# ROV_HAT_sceem.net
KiCad netlist of a schematic drawn in EAGLE
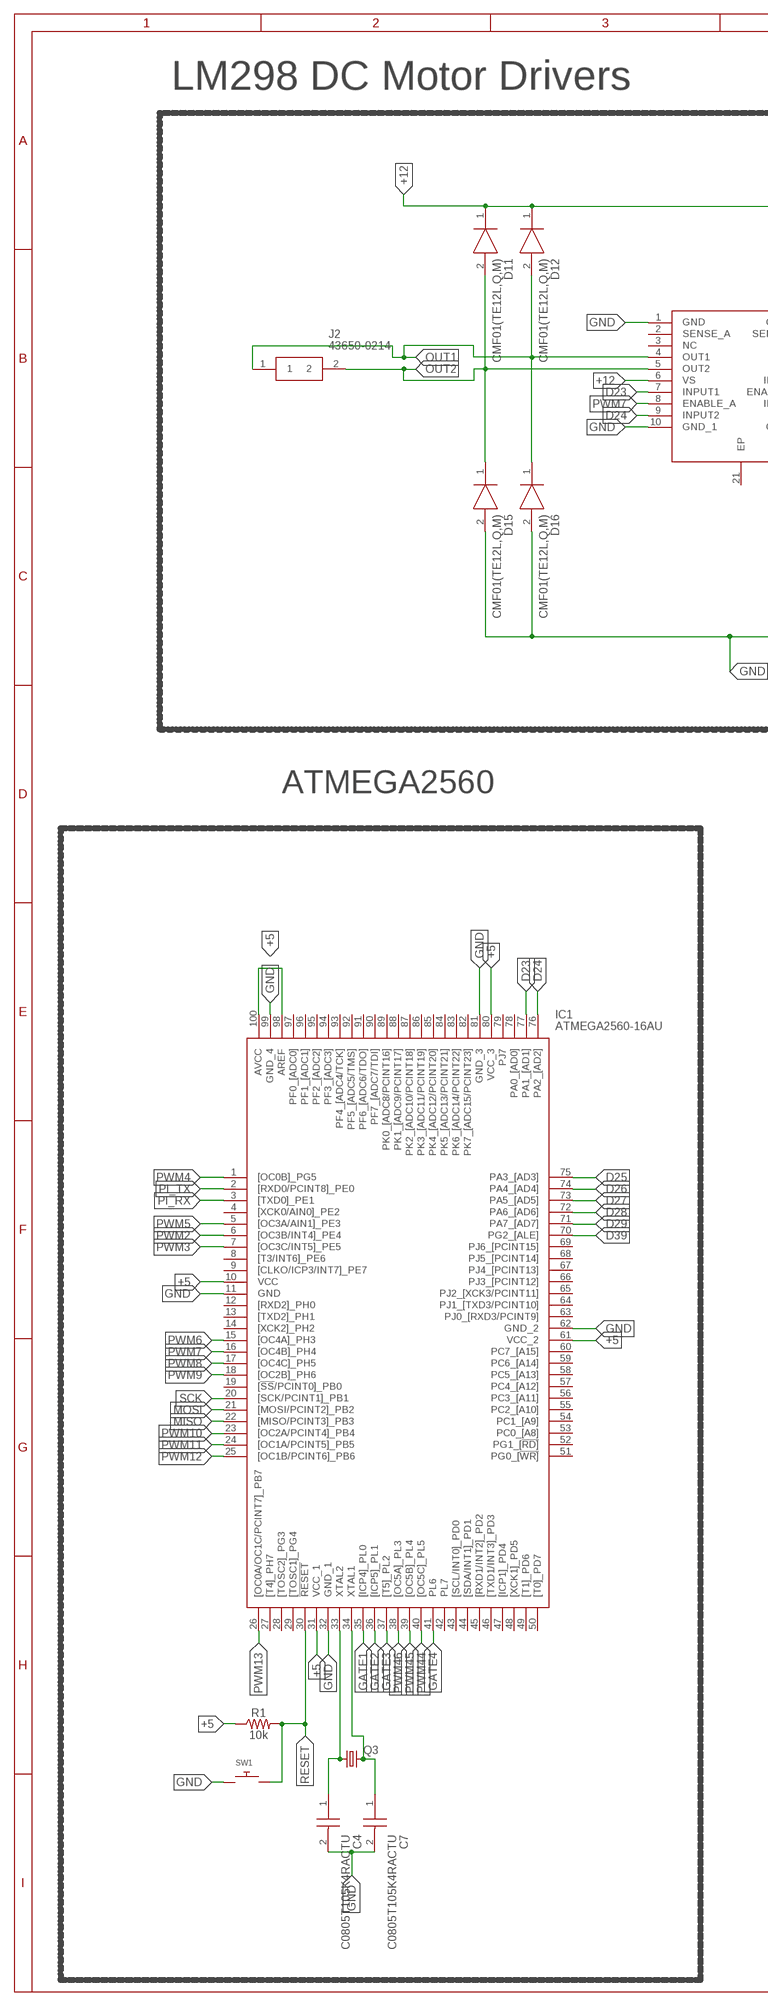
[diagram p0: schematic, sheet 1, part 1 of 2]
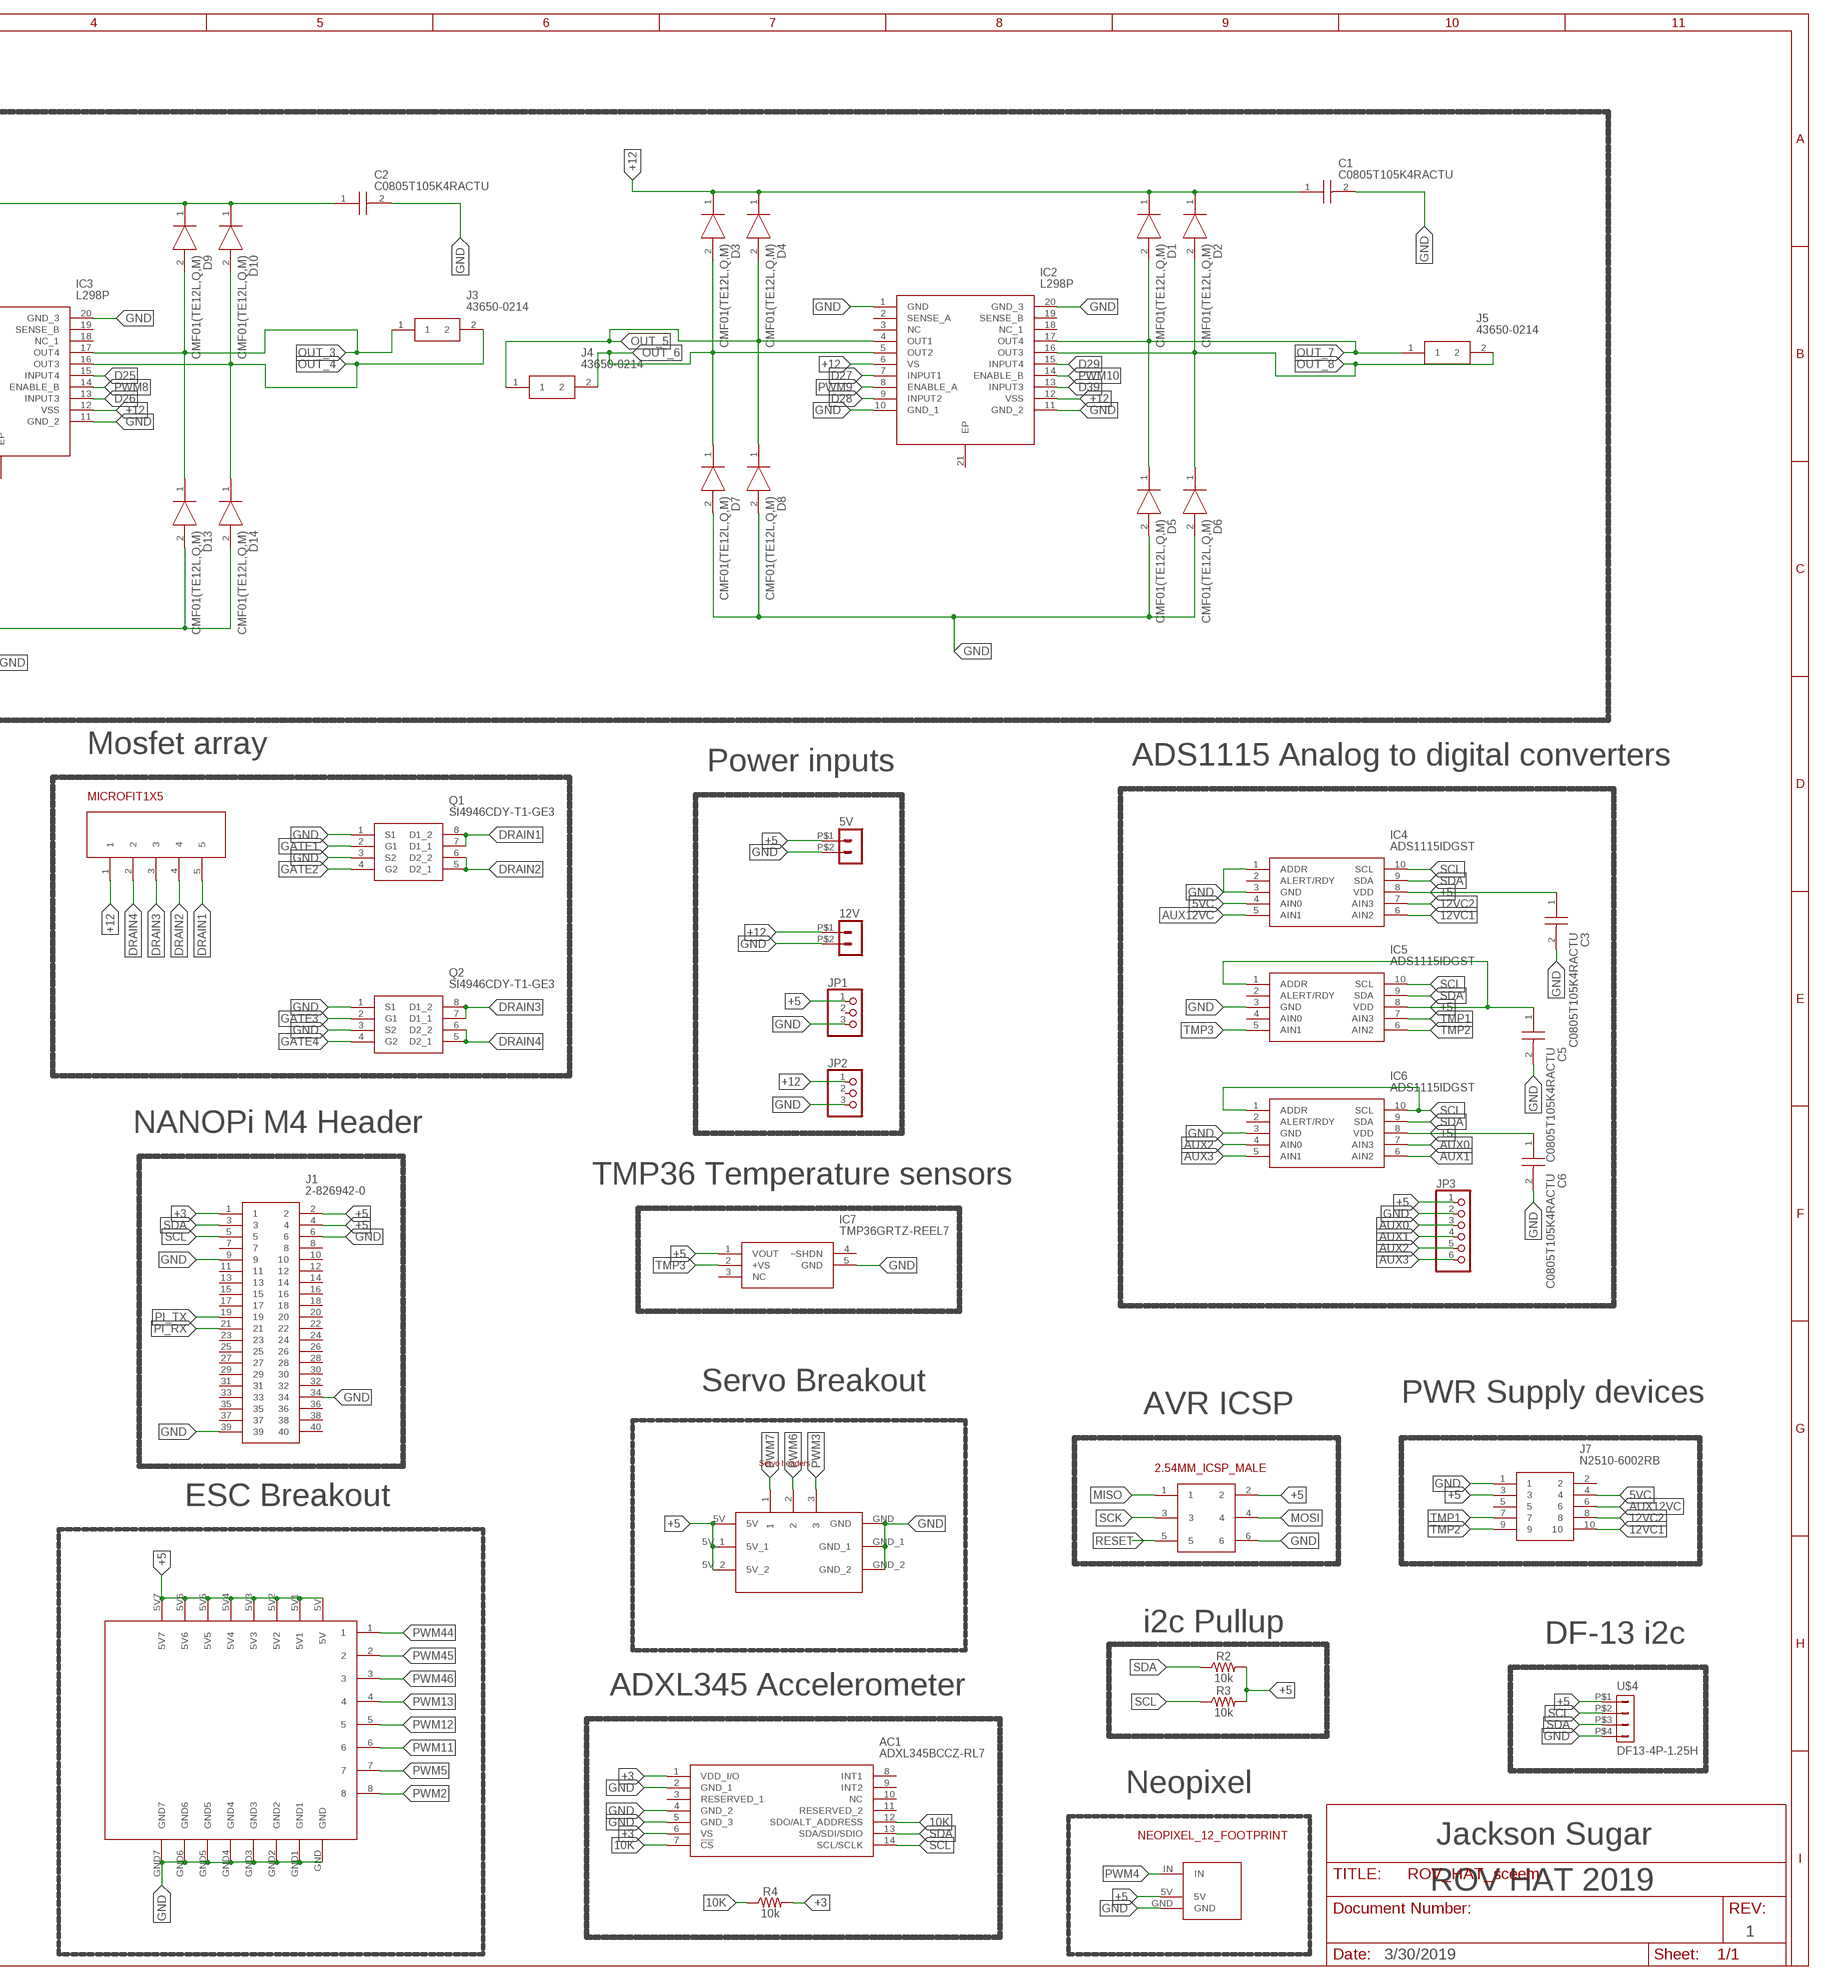
[diagram p1: schematic, sheet 1, part 2 of 2]

(export (version "E")
  (design (tool "Eeschema 10.0.6"))
  (components
    (comp (ref "5V")
      (value "HEADER_POS2_43045-0200")
      (footprint "eagle-import:43045-0200")
      (libsource (lib "eagle-import") (part "HEADER_POS2_?43045-0200"))
    )
    (comp (ref "12V")
      (value "HEADER_POS2_43650-0200")
      (footprint "eagle-import:43650-0200")
      (libsource (lib "eagle-import") (part "HEADER_POS2_?43650-0200"))
    )
    (comp (ref "AC1")
      (value "ADXL345BCCZ-RL7")
      (footprint "eagle-import:CC-14-1")
      (fields (field (name "MOUSER_PART_NUMBER") "584-ADXL345BCCZ-R7"))
      (libsource (lib "eagle-import") (part "ADXL345BCCZ-RL7"))
    )
    (comp (ref "C1")
      (value "C0805T105K4RACTU")
      (footprint "eagle-import:CAPC2012X100N")
      (fields (field (name "MOUSER_PART_NUMBER") "80-C0805T105K4RACTU"))
      (libsource (lib "eagle-import") (part "C0805T105K4RACTU"))
    )
    (comp (ref "C2")
      (value "C0805T105K4RACTU")
      (footprint "eagle-import:CAPC2012X100N")
      (fields (field (name "MOUSER_PART_NUMBER") "80-C0805T105K4RACTU"))
      (libsource (lib "eagle-import") (part "C0805T105K4RACTU"))
    )
    (comp (ref "C3")
      (value "C0805T105K4RACTU")
      (footprint "eagle-import:CAPC2012X100N")
      (fields (field (name "MOUSER_PART_NUMBER") "80-C0805T105K4RACTU"))
      (libsource (lib "eagle-import") (part "C0805T105K4RACTU"))
    )
    (comp (ref "C4")
      (value "C0805T105K4RACTU")
      (footprint "eagle-import:CAPC2012X100N")
      (fields (field (name "MOUSER_PART_NUMBER") "80-C0805T105K4RACTU"))
      (libsource (lib "eagle-import") (part "C0805T105K4RACTU"))
    )
    (comp (ref "C5")
      (value "C0805T105K4RACTU")
      (footprint "eagle-import:CAPC2012X100N")
      (fields (field (name "MOUSER_PART_NUMBER") "80-C0805T105K4RACTU"))
      (libsource (lib "eagle-import") (part "C0805T105K4RACTU"))
    )
    (comp (ref "C6")
      (value "C0805T105K4RACTU")
      (footprint "eagle-import:CAPC2012X100N")
      (fields (field (name "MOUSER_PART_NUMBER") "80-C0805T105K4RACTU"))
      (libsource (lib "eagle-import") (part "C0805T105K4RACTU"))
    )
    (comp (ref "C7")
      (value "C0805T105K4RACTU")
      (footprint "eagle-import:CAPC2012X100N")
      (fields (field (name "MOUSER_PART_NUMBER") "80-C0805T105K4RACTU"))
      (libsource (lib "eagle-import") (part "C0805T105K4RACTU"))
    )
    (comp (ref "D1")
      (value "CMF01(TE12L,Q,M)")
      (footprint "eagle-import:SODFL4724X108N")
      (fields (field (name "MOUSER_PART_NUMBER") "757-CMF01TE12LQM"))
      (libsource (lib "eagle-import") (part "CMF01(TE12L,Q,M)"))
    )
    (comp (ref "D2")
      (value "CMF01(TE12L,Q,M)")
      (footprint "eagle-import:SODFL4724X108N")
      (fields (field (name "MOUSER_PART_NUMBER") "757-CMF01TE12LQM"))
      (libsource (lib "eagle-import") (part "CMF01(TE12L,Q,M)"))
    )
    (comp (ref "D3")
      (value "CMF01(TE12L,Q,M)")
      (footprint "eagle-import:SODFL4724X108N")
      (fields (field (name "MOUSER_PART_NUMBER") "757-CMF01TE12LQM"))
      (libsource (lib "eagle-import") (part "CMF01(TE12L,Q,M)"))
    )
    (comp (ref "D4")
      (value "CMF01(TE12L,Q,M)")
      (footprint "eagle-import:SODFL4724X108N")
      (fields (field (name "MOUSER_PART_NUMBER") "757-CMF01TE12LQM"))
      (libsource (lib "eagle-import") (part "CMF01(TE12L,Q,M)"))
    )
    (comp (ref "D5")
      (value "CMF01(TE12L,Q,M)")
      (footprint "eagle-import:SODFL4724X108N")
      (fields (field (name "MOUSER_PART_NUMBER") "757-CMF01TE12LQM"))
      (libsource (lib "eagle-import") (part "CMF01(TE12L,Q,M)"))
    )
    (comp (ref "D6")
      (value "CMF01(TE12L,Q,M)")
      (footprint "eagle-import:SODFL4724X108N")
      (fields (field (name "MOUSER_PART_NUMBER") "757-CMF01TE12LQM"))
      (libsource (lib "eagle-import") (part "CMF01(TE12L,Q,M)"))
    )
    (comp (ref "D7")
      (value "CMF01(TE12L,Q,M)")
      (footprint "eagle-import:SODFL4724X108N")
      (fields (field (name "MOUSER_PART_NUMBER") "757-CMF01TE12LQM"))
      (libsource (lib "eagle-import") (part "CMF01(TE12L,Q,M)"))
    )
    (comp (ref "D8")
      (value "CMF01(TE12L,Q,M)")
      (footprint "eagle-import:SODFL4724X108N")
      (fields (field (name "MOUSER_PART_NUMBER") "757-CMF01TE12LQM"))
      (libsource (lib "eagle-import") (part "CMF01(TE12L,Q,M)"))
    )
    (comp (ref "D9")
      (value "CMF01(TE12L,Q,M)")
      (footprint "eagle-import:SODFL4724X108N")
      (fields (field (name "MOUSER_PART_NUMBER") "757-CMF01TE12LQM"))
      (libsource (lib "eagle-import") (part "CMF01(TE12L,Q,M)"))
    )
    (comp (ref "D10")
      (value "CMF01(TE12L,Q,M)")
      (footprint "eagle-import:SODFL4724X108N")
      (fields (field (name "MOUSER_PART_NUMBER") "757-CMF01TE12LQM"))
      (libsource (lib "eagle-import") (part "CMF01(TE12L,Q,M)"))
    )
    (comp (ref "D11")
      (value "CMF01(TE12L,Q,M)")
      (footprint "eagle-import:SODFL4724X108N")
      (fields (field (name "MOUSER_PART_NUMBER") "757-CMF01TE12LQM"))
      (libsource (lib "eagle-import") (part "CMF01(TE12L,Q,M)"))
    )
    (comp (ref "D12")
      (value "CMF01(TE12L,Q,M)")
      (footprint "eagle-import:SODFL4724X108N")
      (fields (field (name "MOUSER_PART_NUMBER") "757-CMF01TE12LQM"))
      (libsource (lib "eagle-import") (part "CMF01(TE12L,Q,M)"))
    )
    (comp (ref "D13")
      (value "CMF01(TE12L,Q,M)")
      (footprint "eagle-import:SODFL4724X108N")
      (fields (field (name "MOUSER_PART_NUMBER") "757-CMF01TE12LQM"))
      (libsource (lib "eagle-import") (part "CMF01(TE12L,Q,M)"))
    )
    (comp (ref "D14")
      (value "CMF01(TE12L,Q,M)")
      (footprint "eagle-import:SODFL4724X108N")
      (fields (field (name "MOUSER_PART_NUMBER") "757-CMF01TE12LQM"))
      (libsource (lib "eagle-import") (part "CMF01(TE12L,Q,M)"))
    )
    (comp (ref "D15")
      (value "CMF01(TE12L,Q,M)")
      (footprint "eagle-import:SODFL4724X108N")
      (fields (field (name "MOUSER_PART_NUMBER") "757-CMF01TE12LQM"))
      (libsource (lib "eagle-import") (part "CMF01(TE12L,Q,M)"))
    )
    (comp (ref "D16")
      (value "CMF01(TE12L,Q,M)")
      (footprint "eagle-import:SODFL4724X108N")
      (fields (field (name "MOUSER_PART_NUMBER") "757-CMF01TE12LQM"))
      (libsource (lib "eagle-import") (part "CMF01(TE12L,Q,M)"))
    )
    (comp (ref "IC1")
      (value "ATMEGA2560-16AU")
      (footprint "eagle-import:QFP50P1600X1600X120-100N")
      (fields (field (name "MOUSER_PART_NUMBER") "556-ATMEGA2560-16AU"))
      (libsource (lib "eagle-import") (part "ATMEGA2560-16AU"))
    )
    (comp (ref "IC2")
      (value "L298P")
      (footprint "eagle-import:SOIC127P1420X360-21N")
      (fields (field (name "MOUSER_PART_NUMBER") "511-L298P"))
      (libsource (lib "eagle-import") (part "L298P"))
    )
    (comp (ref "IC3")
      (value "L298P")
      (footprint "eagle-import:SOIC127P1420X360-21N")
      (fields (field (name "MOUSER_PART_NUMBER") "511-L298P"))
      (libsource (lib "eagle-import") (part "L298P"))
    )
    (comp (ref "IC4")
      (value "ADS1115IDGST")
      (footprint "eagle-import:SOP50P490X110-10N")
      (fields (field (name "MOUSER_PART_NUMBER") "595-ADS1115IDGST"))
      (libsource (lib "eagle-import") (part "ADS1115IDGST"))
    )
    (comp (ref "IC5")
      (value "ADS1115IDGST")
      (footprint "eagle-import:SOP50P490X110-10N")
      (fields (field (name "MOUSER_PART_NUMBER") "595-ADS1115IDGST"))
      (libsource (lib "eagle-import") (part "ADS1115IDGST"))
    )
    (comp (ref "IC6")
      (value "ADS1115IDGST")
      (footprint "eagle-import:SOP50P490X110-10N")
      (fields (field (name "MOUSER_PART_NUMBER") "595-ADS1115IDGST"))
      (libsource (lib "eagle-import") (part "ADS1115IDGST"))
    )
    (comp (ref "IC7")
      (value "TMP36GRTZ-REEL7")
      (footprint "eagle-import:SOT95P280X145-5N")
      (fields (field (name "MOUSER_PART_NUMBER") "584-TMP36GRTZ-R7"))
      (libsource (lib "eagle-import") (part "TMP36GRTZ-REEL7"))
    )
    (comp (ref "J1")
      (value "2-826942-0")
      (footprint "eagle-import:HDRV40W63P254_2X20_5080X500X88")
      (fields (field (name "MOUSER_PART_NUMBER") "571-2-826942-0"))
      (libsource (lib "eagle-import") (part "2-826942-0"))
    )
    (comp (ref "J2")
      (value "43650-0214")
      (footprint "eagle-import:43650-0214")
      (fields (field (name "MOUSER_PART_NUMBER") "538-43650-0214"))
      (libsource (lib "eagle-import") (part "43650-0214"))
    )
    (comp (ref "J3")
      (value "43650-0214")
      (footprint "eagle-import:43650-0214")
      (fields (field (name "MOUSER_PART_NUMBER") "538-43650-0214"))
      (libsource (lib "eagle-import") (part "43650-0214"))
    )
    (comp (ref "J4")
      (value "43650-0214")
      (footprint "eagle-import:43650-0214")
      (fields (field (name "MOUSER_PART_NUMBER") "538-43650-0214"))
      (libsource (lib "eagle-import") (part "43650-0214"))
    )
    (comp (ref "J5")
      (value "43650-0214")
      (footprint "eagle-import:43650-0214")
      (fields (field (name "MOUSER_PART_NUMBER") "538-43650-0214"))
      (libsource (lib "eagle-import") (part "43650-0214"))
    )
    (comp (ref "J7")
      (value "N2510-6002RB")
      (footprint "eagle-import:SHDR10W64P254_2X5_2002X859X100")
      (fields (field (name "MOUSER_PART_NUMBER") "517-N2510-6002RB"))
      (libsource (lib "eagle-import") (part "N2510-6002RB"))
    )
    (comp (ref "JP1")
      (value "PINHD-1X3")
      (footprint "eagle-import:1X03")
      (libsource (lib "eagle-import") (part "PINHD-1X3"))
    )
    (comp (ref "JP2")
      (value "PINHD-1X3")
      (footprint "eagle-import:1X03")
      (libsource (lib "eagle-import") (part "PINHD-1X3"))
    )
    (comp (ref "JP3")
      (value "PINHD-1X6")
      (footprint "eagle-import:1X06")
      (libsource (lib "eagle-import") (part "PINHD-1X6"))
    )
    (comp (ref "Q1")
      (value "SI4946CDY-T1-GE3")
      (footprint "eagle-import:SOIC127P600X175-8N")
      (fields (field (name "MOUSER_PART_NUMBER") "78-SI4946CDY-T1-GE3"))
      (libsource (lib "eagle-import") (part "SI4946CDY-T1-GE3"))
    )
    (comp (ref "Q2")
      (value "SI4946CDY-T1-GE3")
      (footprint "eagle-import:SOIC127P600X175-8N")
      (fields (field (name "MOUSER_PART_NUMBER") "78-SI4946CDY-T1-GE3"))
      (libsource (lib "eagle-import") (part "SI4946CDY-T1-GE3"))
    )
    (comp (ref "Q3")
      (value "CRYSTALHC49S")
      (footprint "eagle-import:HC49_S")
      (libsource (lib "eagle-import") (part "CRYSTALHC49S"))
    )
    (comp (ref "R1")
      (value "10k")
      (footprint "eagle-import:0603")
      (libsource (lib "eagle-import") (part "10KOHM-0603-1/10W-1%"))
    )
    (comp (ref "R2")
      (value "10k")
      (footprint "eagle-import:0603")
      (libsource (lib "eagle-import") (part "10KOHM-0603-1/10W-1%"))
    )
    (comp (ref "R3")
      (value "10k")
      (footprint "eagle-import:0603")
      (libsource (lib "eagle-import") (part "10KOHM-0603-1/10W-1%"))
    )
    (comp (ref "R4")
      (value "10k")
      (footprint "eagle-import:0603")
      (libsource (lib "eagle-import") (part "10KOHM-0603-1/10W-1%"))
    )
    (comp (ref "SW1")
      (value "SWITCH_PUSHBUTTONC&K_KSS")
      (footprint "eagle-import:BTN_CK_KSS")
      (libsource (lib "eagle-import") (part "SWITCH_PUSHBUTTONC&K_KSS"))
    )
    (comp (ref "U$1")
      (value "3X8_RIGHT_HEADER")
      (footprint "eagle-import:3X8_RIGHT_HEADER")
      (libsource (lib "eagle-import") (part "3X8_RIGHT_HEADER"))
    )
    (comp (ref "U$2")
      (value "2.54MM_ICSP_MALE")
      (footprint "eagle-import:2.54MM_ICSP_MALE")
      (libsource (lib "eagle-import") (part "2.54MM_ICSP_MALE"))
    )
    (comp (ref "U$3")
      (value "NEOPIXEL_12_FOOTPRINT")
      (footprint "eagle-import:NEOPIXEL_12_FOOTPRINT")
      (libsource (lib "eagle-import") (part "NEOPIXEL_12_FOOTPRINT"))
    )
    (comp (ref "U$4")
      (value "DF13-4P-1.25H")
      (footprint "eagle-import:DF13A-4P-1.25H")
      (libsource (lib "eagle-import") (part "DF13-4P-1.25H"))
    )
    (comp (ref "U$5")
      (value "SERVO_PWM_HEADER")
      (footprint "eagle-import:SERVO_PWM_HEADER")
      (libsource (lib "eagle-import") (part "SERVO_PWM_HEADER"))
    )
    (comp (ref "U$6")
      (value "MICROFIT1X5")
      (footprint "eagle-import:MICROFIT1X5")
      (libsource (lib "eagle-import") (part "MICROFIT1X5"))
    )
  )
  (nets
    (net (code "1") (name "+3") (class "Default")
      (node (ref "AC1") (pin "1") (pinfunction "VDD_I/O_1") (pintype "bidirectional"))
      (node (ref "AC1") (pin "6") (pinfunction "VS_6") (pintype "bidirectional"))
      (node (ref "J1") (pin "1") (pinfunction "1_1") (pintype "bidirectional"))
      (node (ref "R4") (pin "2") (pinfunction "2_2") (pintype "passive"))
    )
    (net (code "2") (name "+5") (class "Default")
      (node (ref "5V") (pin "P$1") (pinfunction "1_P$1") (pintype "passive"))
      (node (ref "C3") (pin "1") (pinfunction "1_1") (pintype "bidirectional"))
      (node (ref "C5") (pin "1") (pinfunction "1_1") (pintype "bidirectional"))
      (node (ref "C6") (pin "1") (pinfunction "1_1") (pintype "bidirectional"))
      (node (ref "IC1") (pin "10") (pinfunction "VCC_10") (pintype "power_in"))
      (node (ref "IC1") (pin "100") (pinfunction "AVCC_100") (pintype "power_in"))
      (node (ref "IC1") (pin "31") (pinfunction "VCC_1_31") (pintype "power_in"))
      (node (ref "IC1") (pin "61") (pinfunction "VCC_2_61") (pintype "power_in"))
      (node (ref "IC1") (pin "80") (pinfunction "VCC_3_80") (pintype "power_in"))
      (node (ref "IC1") (pin "98") (pinfunction "AREF_98") (pintype "input"))
      (node (ref "IC4") (pin "8") (pinfunction "VDD_8") (pintype "power_in"))
      (node (ref "IC5") (pin "1") (pinfunction "ADDR_1") (pintype "bidirectional"))
      (node (ref "IC5") (pin "8") (pinfunction "VDD_8") (pintype "power_in"))
      (node (ref "IC6") (pin "8") (pinfunction "VDD_8") (pintype "power_in"))
      (node (ref "IC7") (pin "1") (pinfunction "VOUT_1") (pintype "bidirectional"))
      (node (ref "J1") (pin "2") (pinfunction "2_2") (pintype "bidirectional"))
      (node (ref "J1") (pin "4") (pinfunction "4_4") (pintype "bidirectional"))
      (node (ref "J7") (pin "3") (pinfunction "3_3") (pintype "bidirectional"))
      (node (ref "JP1") (pin "1") (pinfunction "1_1") (pintype "passive"))
      (node (ref "JP3") (pin "1") (pinfunction "1_1") (pintype "passive"))
      (node (ref "R1") (pin "1") (pinfunction "1_1") (pintype "passive"))
      (node (ref "R2") (pin "2") (pinfunction "2_2") (pintype "passive"))
      (node (ref "R3") (pin "2") (pinfunction "2_2") (pintype "passive"))
      (node (ref "U$1") (pin "5V") (pinfunction "5V_5V") (pintype "bidirectional"))
      (node (ref "U$1") (pin "5V1") (pinfunction "5V1_5V1") (pintype "bidirectional"))
      (node (ref "U$1") (pin "5V2") (pinfunction "5V2_5V2") (pintype "bidirectional"))
      (node (ref "U$1") (pin "5V3") (pinfunction "5V3_5V3") (pintype "bidirectional"))
      (node (ref "U$1") (pin "5V4") (pinfunction "5V4_5V4") (pintype "bidirectional"))
      (node (ref "U$1") (pin "5V5") (pinfunction "5V5_5V5") (pintype "bidirectional"))
      (node (ref "U$1") (pin "5V6") (pinfunction "5V6_5V6") (pintype "bidirectional"))
      (node (ref "U$1") (pin "5V7") (pinfunction "5V7_5V7") (pintype "bidirectional"))
      (node (ref "U$2") (pin "2") (pinfunction "2_2") (pintype "bidirectional"))
      (node (ref "U$3") (pin "5V") (pinfunction "5V_5V") (pintype "bidirectional"))
      (node (ref "U$4") (pin "P$1") (pinfunction "1_P$1") (pintype "passive"))
      (node (ref "U$5") (pin "5V") (pinfunction "5V_5V") (pintype "bidirectional"))
      (node (ref "U$5") (pin "5V_1") (pinfunction "5V_1_5V_1") (pintype "bidirectional"))
      (node (ref "U$5") (pin "5V_2") (pinfunction "5V_2_5V_2") (pintype "bidirectional"))
    )
    (net (code "3") (name "+12") (class "Default")
      (node (ref "12V") (pin "P$1") (pinfunction "1_P$1") (pintype "passive"))
      (node (ref "C1") (pin "1") (pinfunction "1_1") (pintype "bidirectional"))
      (node (ref "C2") (pin "1") (pinfunction "1_1") (pintype "bidirectional"))
      (node (ref "D1") (pin "1") (pinfunction "K_1") (pintype "bidirectional"))
      (node (ref "D10") (pin "1") (pinfunction "K_1") (pintype "bidirectional"))
      (node (ref "D11") (pin "1") (pinfunction "K_1") (pintype "bidirectional"))
      (node (ref "D12") (pin "1") (pinfunction "K_1") (pintype "bidirectional"))
      (node (ref "D2") (pin "1") (pinfunction "K_1") (pintype "bidirectional"))
      (node (ref "D3") (pin "1") (pinfunction "K_1") (pintype "bidirectional"))
      (node (ref "D4") (pin "1") (pinfunction "K_1") (pintype "bidirectional"))
      (node (ref "D9") (pin "1") (pinfunction "K_1") (pintype "bidirectional"))
      (node (ref "IC2") (pin "12") (pinfunction "VSS_12") (pintype "power_in"))
      (node (ref "IC2") (pin "6") (pinfunction "VS_6") (pintype "power_in"))
      (node (ref "IC3") (pin "12") (pinfunction "VSS_12") (pintype "power_in"))
      (node (ref "IC3") (pin "6") (pinfunction "VS_6") (pintype "power_in"))
      (node (ref "JP2") (pin "1") (pinfunction "1_1") (pintype "passive"))
      (node (ref "U$6") (pin "1") (pinfunction "1_1") (pintype "bidirectional"))
    )
    (net (code "4") (name "5VC") (class "Default")
      (node (ref "IC4") (pin "4") (pinfunction "AIN0_4") (pintype "input"))
      (node (ref "J7") (pin "4") (pinfunction "4_4") (pintype "bidirectional"))
    )
    (net (code "5") (name "10K") (class "Default")
      (node (ref "AC1") (pin "12") (pinfunction "SDO/ALT_ADDRESS_12") (pintype "bidirectional"))
      (node (ref "AC1") (pin "7") (pinfunction "~{CS}_7") (pintype "bidirectional"))
      (node (ref "R4") (pin "1") (pinfunction "1_1") (pintype "passive"))
    )
    (net (code "6") (name "12VC1") (class "Default")
      (node (ref "IC4") (pin "6") (pinfunction "AIN2_6") (pintype "input"))
      (node (ref "J7") (pin "10") (pinfunction "10_10") (pintype "bidirectional"))
    )
    (net (code "7") (name "12VC2") (class "Default")
      (node (ref "IC4") (pin "7") (pinfunction "AIN3_7") (pintype "input"))
      (node (ref "J7") (pin "8") (pinfunction "8_8") (pintype "bidirectional"))
    )
    (net (code "8") (name "AUX0") (class "Default")
      (node (ref "IC6") (pin "7") (pinfunction "AIN3_7") (pintype "input"))
      (node (ref "JP3") (pin "3") (pinfunction "3_3") (pintype "passive"))
    )
    (net (code "9") (name "AUX1") (class "Default")
      (node (ref "IC6") (pin "6") (pinfunction "AIN2_6") (pintype "input"))
      (node (ref "JP3") (pin "4") (pinfunction "4_4") (pintype "passive"))
    )
    (net (code "10") (name "AUX2") (class "Default")
      (node (ref "IC6") (pin "4") (pinfunction "AIN0_4") (pintype "input"))
      (node (ref "JP3") (pin "5") (pinfunction "5_5") (pintype "passive"))
    )
    (net (code "11") (name "AUX3") (class "Default")
      (node (ref "IC6") (pin "5") (pinfunction "AIN1_5") (pintype "input"))
      (node (ref "JP3") (pin "6") (pinfunction "6_6") (pintype "passive"))
    )
    (net (code "12") (name "AUX12VC") (class "Default")
      (node (ref "IC4") (pin "5") (pinfunction "AIN1_5") (pintype "input"))
      (node (ref "J7") (pin "6") (pinfunction "6_6") (pintype "bidirectional"))
    )
    (net (code "13") (name "D23") (class "Default")
      (node (ref "IC1") (pin "77") (pinfunction "PA1_[AD1]_77") (pintype "bidirectional"))
      (node (ref "IC3") (pin "7") (pinfunction "INPUT1_7") (pintype "input"))
    )
    (net (code "14") (name "D24") (class "Default")
      (node (ref "IC1") (pin "76") (pinfunction "PA2_[AD2]_76") (pintype "bidirectional"))
      (node (ref "IC3") (pin "9") (pinfunction "INPUT2_9") (pintype "input"))
    )
    (net (code "15") (name "D25") (class "Default")
      (node (ref "IC1") (pin "75") (pinfunction "PA3_[AD3]_75") (pintype "bidirectional"))
      (node (ref "IC3") (pin "15") (pinfunction "INPUT4_15") (pintype "input"))
    )
    (net (code "16") (name "D26") (class "Default")
      (node (ref "IC1") (pin "74") (pinfunction "PA4_[AD4]_74") (pintype "bidirectional"))
      (node (ref "IC3") (pin "13") (pinfunction "INPUT3_13") (pintype "input"))
    )
    (net (code "17") (name "D27") (class "Default")
      (node (ref "IC1") (pin "73") (pinfunction "PA5_[AD5]_73") (pintype "bidirectional"))
      (node (ref "IC2") (pin "7") (pinfunction "INPUT1_7") (pintype "input"))
    )
    (net (code "18") (name "D28") (class "Default")
      (node (ref "IC1") (pin "72") (pinfunction "PA6_[AD6]_72") (pintype "bidirectional"))
      (node (ref "IC2") (pin "9") (pinfunction "INPUT2_9") (pintype "input"))
    )
    (net (code "19") (name "D29") (class "Default")
      (node (ref "IC1") (pin "71") (pinfunction "PA7_[AD7]_71") (pintype "bidirectional"))
      (node (ref "IC2") (pin "15") (pinfunction "INPUT4_15") (pintype "input"))
    )
    (net (code "20") (name "D39") (class "Default")
      (node (ref "IC1") (pin "70") (pinfunction "PG2_[ALE]_70") (pintype "bidirectional"))
      (node (ref "IC2") (pin "13") (pinfunction "INPUT3_13") (pintype "input"))
    )
    (net (code "21") (name "DRAIN1") (class "Default")
      (node (ref "Q1") (pin "7") (pinfunction "D1_1_7") (pintype "bidirectional"))
      (node (ref "Q1") (pin "8") (pinfunction "D1_2_8") (pintype "bidirectional"))
      (node (ref "U$6") (pin "5") (pinfunction "5_5") (pintype "bidirectional"))
    )
    (net (code "22") (name "DRAIN2") (class "Default")
      (node (ref "Q1") (pin "5") (pinfunction "D2_1_5") (pintype "bidirectional"))
      (node (ref "Q1") (pin "6") (pinfunction "D2_2_6") (pintype "bidirectional"))
      (node (ref "U$6") (pin "4") (pinfunction "4_4") (pintype "bidirectional"))
    )
    (net (code "23") (name "DRAIN3") (class "Default")
      (node (ref "Q2") (pin "7") (pinfunction "D1_1_7") (pintype "bidirectional"))
      (node (ref "Q2") (pin "8") (pinfunction "D1_2_8") (pintype "bidirectional"))
      (node (ref "U$6") (pin "3") (pinfunction "3_3") (pintype "bidirectional"))
    )
    (net (code "24") (name "DRAIN4") (class "Default")
      (node (ref "Q2") (pin "5") (pinfunction "D2_1_5") (pintype "bidirectional"))
      (node (ref "Q2") (pin "6") (pinfunction "D2_2_6") (pintype "bidirectional"))
      (node (ref "U$6") (pin "2") (pinfunction "2_2") (pintype "bidirectional"))
    )
    (net (code "25") (name "GATE1") (class "Default")
      (node (ref "IC1") (pin "35") (pinfunction "[ICP4]_PL0_35") (pintype "bidirectional"))
      (node (ref "Q1") (pin "2") (pinfunction "G1_2") (pintype "bidirectional"))
    )
    (net (code "26") (name "GATE2") (class "Default")
      (node (ref "IC1") (pin "36") (pinfunction "[ICP5]_PL1_36") (pintype "bidirectional"))
      (node (ref "Q1") (pin "4") (pinfunction "G2_4") (pintype "bidirectional"))
    )
    (net (code "27") (name "GATE3") (class "Default")
      (node (ref "IC1") (pin "37") (pinfunction "[T5]_PL2_37") (pintype "bidirectional"))
      (node (ref "Q2") (pin "2") (pinfunction "G1_2") (pintype "bidirectional"))
    )
    (net (code "28") (name "GATE4") (class "Default")
      (node (ref "IC1") (pin "41") (pinfunction "PL6_41") (pintype "bidirectional"))
      (node (ref "Q2") (pin "4") (pinfunction "G2_4") (pintype "bidirectional"))
    )
    (net (code "29") (name "GND") (class "Default")
      (node (ref "12V") (pin "P$2") (pinfunction "2_P$2") (pintype "passive"))
      (node (ref "5V") (pin "P$2") (pinfunction "2_P$2") (pintype "passive"))
      (node (ref "AC1") (pin "2") (pinfunction "GND_1_2") (pintype "bidirectional"))
      (node (ref "AC1") (pin "4") (pinfunction "GND_2_4") (pintype "bidirectional"))
      (node (ref "AC1") (pin "5") (pinfunction "GND_3_5") (pintype "bidirectional"))
      (node (ref "C1") (pin "2") (pinfunction "2_2") (pintype "bidirectional"))
      (node (ref "C2") (pin "2") (pinfunction "2_2") (pintype "bidirectional"))
      (node (ref "C3") (pin "2") (pinfunction "2_2") (pintype "bidirectional"))
      (node (ref "C4") (pin "2") (pinfunction "2_2") (pintype "bidirectional"))
      (node (ref "C5") (pin "2") (pinfunction "2_2") (pintype "bidirectional"))
      (node (ref "C6") (pin "2") (pinfunction "2_2") (pintype "bidirectional"))
      (node (ref "C7") (pin "2") (pinfunction "2_2") (pintype "bidirectional"))
      (node (ref "D13") (pin "2") (pinfunction "A_2") (pintype "bidirectional"))
      (node (ref "D14") (pin "2") (pinfunction "A_2") (pintype "bidirectional"))
      (node (ref "D15") (pin "2") (pinfunction "A_2") (pintype "bidirectional"))
      (node (ref "D16") (pin "2") (pinfunction "A_2") (pintype "bidirectional"))
      (node (ref "D5") (pin "2") (pinfunction "A_2") (pintype "bidirectional"))
      (node (ref "D6") (pin "2") (pinfunction "A_2") (pintype "bidirectional"))
      (node (ref "D7") (pin "2") (pinfunction "A_2") (pintype "bidirectional"))
      (node (ref "D8") (pin "2") (pinfunction "A_2") (pintype "bidirectional"))
      (node (ref "IC1") (pin "11") (pinfunction "GND_11") (pintype "power_in"))
      (node (ref "IC1") (pin "32") (pinfunction "GND_1_32") (pintype "power_in"))
      (node (ref "IC1") (pin "62") (pinfunction "GND_2_62") (pintype "power_in"))
      (node (ref "IC1") (pin "81") (pinfunction "GND_3_81") (pintype "power_in"))
      (node (ref "IC1") (pin "99") (pinfunction "GND_4_99") (pintype "power_in"))
      (node (ref "IC2") (pin "1") (pinfunction "GND_1") (pintype "power_in"))
      (node (ref "IC2") (pin "10") (pinfunction "GND_1_10") (pintype "power_in"))
      (node (ref "IC2") (pin "11") (pinfunction "GND_2_11") (pintype "power_in"))
      (node (ref "IC2") (pin "20") (pinfunction "GND_3_20") (pintype "power_in"))
      (node (ref "IC3") (pin "1") (pinfunction "GND_1") (pintype "power_in"))
      (node (ref "IC3") (pin "10") (pinfunction "GND_1_10") (pintype "power_in"))
      (node (ref "IC3") (pin "11") (pinfunction "GND_2_11") (pintype "power_in"))
      (node (ref "IC3") (pin "20") (pinfunction "GND_3_20") (pintype "power_in"))
      (node (ref "IC4") (pin "1") (pinfunction "ADDR_1") (pintype "bidirectional"))
      (node (ref "IC4") (pin "3") (pinfunction "GND_3") (pintype "power_in"))
      (node (ref "IC5") (pin "3") (pinfunction "GND_3") (pintype "power_in"))
      (node (ref "IC6") (pin "3") (pinfunction "GND_3") (pintype "power_in"))
      (node (ref "IC7") (pin "5") (pinfunction "GND_5") (pintype "bidirectional"))
      (node (ref "J1") (pin "34") (pinfunction "34_34") (pintype "bidirectional"))
      (node (ref "J1") (pin "39") (pinfunction "39_39") (pintype "bidirectional"))
      (node (ref "J1") (pin "6") (pinfunction "6_6") (pintype "bidirectional"))
      (node (ref "J1") (pin "9") (pinfunction "9_9") (pintype "bidirectional"))
      (node (ref "J7") (pin "1") (pinfunction "1_1") (pintype "bidirectional"))
      (node (ref "JP1") (pin "3") (pinfunction "3_3") (pintype "passive"))
      (node (ref "JP2") (pin "3") (pinfunction "3_3") (pintype "passive"))
      (node (ref "JP3") (pin "2") (pinfunction "2_2") (pintype "passive"))
      (node (ref "Q1") (pin "1") (pinfunction "S1_1") (pintype "bidirectional"))
      (node (ref "Q1") (pin "3") (pinfunction "S2_3") (pintype "bidirectional"))
      (node (ref "Q2") (pin "1") (pinfunction "S1_1") (pintype "bidirectional"))
      (node (ref "Q2") (pin "3") (pinfunction "S2_3") (pintype "bidirectional"))
      (node (ref "SW1") (pin "P$1") (pinfunction "P$1_P$1") (pintype "passive"))
      (node (ref "U$1") (pin "GND") (pinfunction "GND_GND") (pintype "bidirectional"))
      (node (ref "U$1") (pin "GND1") (pinfunction "GND1_GND1") (pintype "bidirectional"))
      (node (ref "U$1") (pin "GND2") (pinfunction "GND2_GND2") (pintype "bidirectional"))
      (node (ref "U$1") (pin "GND3") (pinfunction "GND3_GND3") (pintype "bidirectional"))
      (node (ref "U$1") (pin "GND4") (pinfunction "GND4_GND4") (pintype "bidirectional"))
      (node (ref "U$1") (pin "GND5") (pinfunction "GND5_GND5") (pintype "bidirectional"))
      (node (ref "U$1") (pin "GND6") (pinfunction "GND6_GND6") (pintype "bidirectional"))
      (node (ref "U$1") (pin "GND7") (pinfunction "GND7_GND7") (pintype "bidirectional"))
      (node (ref "U$2") (pin "6") (pinfunction "6_6") (pintype "bidirectional"))
      (node (ref "U$3") (pin "GND") (pinfunction "GND_GND") (pintype "bidirectional"))
      (node (ref "U$4") (pin "P$4") (pinfunction "4_P$4") (pintype "passive"))
      (node (ref "U$5") (pin "GND") (pinfunction "GND_GND") (pintype "bidirectional"))
      (node (ref "U$5") (pin "GND_1") (pinfunction "GND_1_GND_1") (pintype "bidirectional"))
      (node (ref "U$5") (pin "GND_2") (pinfunction "GND_2_GND_2") (pintype "bidirectional"))
    )
    (net (code "30") (name "MISO") (class "Default")
      (node (ref "IC1") (pin "22") (pinfunction "[MISO/PCINT3]_PB3_22") (pintype "input"))
      (node (ref "U$2") (pin "1") (pinfunction "1_1") (pintype "bidirectional"))
    )
    (net (code "31") (name "MOSI") (class "Default")
      (node (ref "IC1") (pin "21") (pinfunction "[MOSI/PCINT2]_PB2_21") (pintype "input"))
      (node (ref "U$2") (pin "4") (pinfunction "4_4") (pintype "bidirectional"))
    )
    (net (code "32") (name "Net-(IC1-XTAL1)") (class "Default")
      (node (ref "C7") (pin "1") (pinfunction "1_1") (pintype "bidirectional"))
      (node (ref "IC1") (pin "34") (pinfunction "XTAL1_34") (pintype "bidirectional"))
      (node (ref "Q3") (pin "2") (pinfunction "2_2") (pintype "passive"))
    )
    (net (code "33") (name "Net-(IC1-XTAL2)") (class "Default")
      (node (ref "C4") (pin "1") (pinfunction "1_1") (pintype "bidirectional"))
      (node (ref "IC1") (pin "33") (pinfunction "XTAL2_33") (pintype "bidirectional"))
      (node (ref "Q3") (pin "1") (pinfunction "1_1") (pintype "passive"))
    )
    (net (code "34") (name "OUT1") (class "Default")
      (node (ref "D12") (pin "2") (pinfunction "A_2") (pintype "bidirectional"))
      (node (ref "D16") (pin "1") (pinfunction "K_1") (pintype "bidirectional"))
      (node (ref "IC3") (pin "4") (pinfunction "OUT1_4") (pintype "output"))
      (node (ref "J2") (pin "1") (pinfunction "1_1") (pintype "bidirectional"))
    )
    (net (code "35") (name "OUT2") (class "Default")
      (node (ref "D11") (pin "2") (pinfunction "A_2") (pintype "bidirectional"))
      (node (ref "D15") (pin "1") (pinfunction "K_1") (pintype "bidirectional"))
      (node (ref "IC3") (pin "5") (pinfunction "OUT2_5") (pintype "output"))
      (node (ref "J2") (pin "2") (pinfunction "2_2") (pintype "bidirectional"))
    )
    (net (code "36") (name "OUT_3") (class "Default")
      (node (ref "D13") (pin "1") (pinfunction "K_1") (pintype "bidirectional"))
      (node (ref "D9") (pin "2") (pinfunction "A_2") (pintype "bidirectional"))
      (node (ref "IC3") (pin "17") (pinfunction "OUT4_17") (pintype "output"))
      (node (ref "J3") (pin "1") (pinfunction "1_1") (pintype "bidirectional"))
    )
    (net (code "37") (name "OUT_4") (class "Default")
      (node (ref "D10") (pin "2") (pinfunction "A_2") (pintype "bidirectional"))
      (node (ref "D14") (pin "1") (pinfunction "K_1") (pintype "bidirectional"))
      (node (ref "IC3") (pin "16") (pinfunction "OUT3_16") (pintype "output"))
      (node (ref "J3") (pin "2") (pinfunction "2_2") (pintype "bidirectional"))
    )
    (net (code "38") (name "OUT_5") (class "Default")
      (node (ref "D4") (pin "2") (pinfunction "A_2") (pintype "bidirectional"))
      (node (ref "D8") (pin "1") (pinfunction "K_1") (pintype "bidirectional"))
      (node (ref "IC2") (pin "4") (pinfunction "OUT1_4") (pintype "output"))
      (node (ref "J4") (pin "1") (pinfunction "1_1") (pintype "bidirectional"))
    )
    (net (code "39") (name "OUT_6") (class "Default")
      (node (ref "D3") (pin "2") (pinfunction "A_2") (pintype "bidirectional"))
      (node (ref "D7") (pin "1") (pinfunction "K_1") (pintype "bidirectional"))
      (node (ref "IC2") (pin "5") (pinfunction "OUT2_5") (pintype "output"))
      (node (ref "J4") (pin "2") (pinfunction "2_2") (pintype "bidirectional"))
    )
    (net (code "40") (name "OUT_7") (class "Default")
      (node (ref "D1") (pin "2") (pinfunction "A_2") (pintype "bidirectional"))
      (node (ref "D5") (pin "1") (pinfunction "K_1") (pintype "bidirectional"))
      (node (ref "IC2") (pin "17") (pinfunction "OUT4_17") (pintype "output"))
      (node (ref "J5") (pin "1") (pinfunction "1_1") (pintype "bidirectional"))
    )
    (net (code "41") (name "OUT_8") (class "Default")
      (node (ref "D2") (pin "2") (pinfunction "A_2") (pintype "bidirectional"))
      (node (ref "D6") (pin "1") (pinfunction "K_1") (pintype "bidirectional"))
      (node (ref "IC2") (pin "16") (pinfunction "OUT3_16") (pintype "output"))
      (node (ref "J5") (pin "2") (pinfunction "2_2") (pintype "bidirectional"))
    )
    (net (code "42") (name "PI_RX") (class "Default")
      (node (ref "IC1") (pin "3") (pinfunction "[TXD0]_PE1_3") (pintype "bidirectional"))
      (node (ref "J1") (pin "21") (pinfunction "21_21") (pintype "bidirectional"))
    )
    (net (code "43") (name "PI_TX") (class "Default")
      (node (ref "IC1") (pin "2") (pinfunction "[RXD0/PCINT8]_PE0_2") (pintype "input"))
      (node (ref "J1") (pin "19") (pinfunction "19_19") (pintype "bidirectional"))
    )
    (net (code "44") (name "PWM2") (class "Default")
      (node (ref "IC1") (pin "6") (pinfunction "[OC3B/INT4]_PE4_6") (pintype "input"))
      (node (ref "U$1") (pin "8") (pinfunction "8_8") (pintype "bidirectional"))
    )
    (net (code "45") (name "PWM3") (class "Default")
      (node (ref "IC1") (pin "7") (pinfunction "[OC3C/INT5]_PE5_7") (pintype "input"))
      (node (ref "U$5") (pin "3") (pinfunction "3_3") (pintype "bidirectional"))
    )
    (net (code "46") (name "PWM4") (class "Default")
      (node (ref "IC1") (pin "1") (pinfunction "[OC0B]_PG5_1") (pintype "bidirectional"))
      (node (ref "U$3") (pin "IN") (pinfunction "IN_IN") (pintype "bidirectional"))
    )
    (net (code "47") (name "PWM5") (class "Default")
      (node (ref "IC1") (pin "5") (pinfunction "[OC3A/AIN1]_PE3_5") (pintype "input"))
      (node (ref "U$1") (pin "7") (pinfunction "7_7") (pintype "bidirectional"))
    )
    (net (code "48") (name "PWM6") (class "Default")
      (node (ref "IC1") (pin "15") (pinfunction "[OC4A]_PH3_15") (pintype "bidirectional"))
      (node (ref "U$5") (pin "2") (pinfunction "2_2") (pintype "bidirectional"))
    )
    (net (code "49") (name "PWM7") (class "Default")
      (node (ref "IC1") (pin "16") (pinfunction "[OC4B]_PH4_16") (pintype "bidirectional"))
      (node (ref "IC3") (pin "8") (pinfunction "ENABLE_A_8") (pintype "input"))
      (node (ref "U$5") (pin "1") (pinfunction "1_1") (pintype "bidirectional"))
    )
    (net (code "50") (name "PWM8") (class "Default")
      (node (ref "IC1") (pin "17") (pinfunction "[OC4C]_PH5_17") (pintype "bidirectional"))
      (node (ref "IC3") (pin "14") (pinfunction "ENABLE_B_14") (pintype "input"))
    )
    (net (code "51") (name "PWM9") (class "Default")
      (node (ref "IC1") (pin "18") (pinfunction "[OC2B]_PH6_18") (pintype "bidirectional"))
      (node (ref "IC2") (pin "8") (pinfunction "ENABLE_A_8") (pintype "input"))
    )
    (net (code "52") (name "PWM10") (class "Default")
      (node (ref "IC1") (pin "23") (pinfunction "[OC2A/PCINT4]_PB4_23") (pintype "input"))
      (node (ref "IC2") (pin "14") (pinfunction "ENABLE_B_14") (pintype "input"))
    )
    (net (code "53") (name "PWM11") (class "Default")
      (node (ref "IC1") (pin "24") (pinfunction "[OC1A/PCINT5]_PB5_24") (pintype "input"))
      (node (ref "U$1") (pin "6") (pinfunction "6_6") (pintype "bidirectional"))
    )
    (net (code "54") (name "PWM12") (class "Default")
      (node (ref "IC1") (pin "25") (pinfunction "[OC1B/PCINT6]_PB6_25") (pintype "input"))
      (node (ref "U$1") (pin "5") (pinfunction "5_5") (pintype "bidirectional"))
    )
    (net (code "55") (name "PWM13") (class "Default")
      (node (ref "IC1") (pin "26") (pinfunction "[OC0A/OC1C/PCINT7]_PB7_26") (pintype "input"))
      (node (ref "U$1") (pin "4") (pinfunction "4_4") (pintype "bidirectional"))
    )
    (net (code "56") (name "PWM44") (class "Default")
      (node (ref "IC1") (pin "40") (pinfunction "[OC5C]_PL5_40") (pintype "bidirectional"))
      (node (ref "U$1") (pin "1") (pinfunction "1_1") (pintype "bidirectional"))
    )
    (net (code "57") (name "PWM45") (class "Default")
      (node (ref "IC1") (pin "39") (pinfunction "[OC5B]_PL4_39") (pintype "bidirectional"))
      (node (ref "U$1") (pin "2") (pinfunction "2_2") (pintype "bidirectional"))
    )
    (net (code "58") (name "PWM46") (class "Default")
      (node (ref "IC1") (pin "38") (pinfunction "[OC5A]_PL3_38") (pintype "bidirectional"))
      (node (ref "U$1") (pin "3") (pinfunction "3_3") (pintype "bidirectional"))
    )
    (net (code "59") (name "RESET") (class "Default")
      (node (ref "IC1") (pin "30") (pinfunction "~{RESET}_30") (pintype "bidirectional"))
      (node (ref "R1") (pin "2") (pinfunction "2_2") (pintype "passive"))
      (node (ref "SW1") (pin "P$2") (pinfunction "P$2_P$2") (pintype "passive"))
      (node (ref "U$2") (pin "5") (pinfunction "5_5") (pintype "bidirectional"))
    )
    (net (code "60") (name "SCK") (class "Default")
      (node (ref "IC1") (pin "20") (pinfunction "[SCK/PCINT1]_PB1_20") (pintype "input"))
      (node (ref "U$2") (pin "3") (pinfunction "3_3") (pintype "bidirectional"))
    )
    (net (code "61") (name "SCL") (class "Default")
      (node (ref "AC1") (pin "14") (pinfunction "SCL/SCLK_14") (pintype "bidirectional"))
      (node (ref "IC4") (pin "10") (pinfunction "SCL_10") (pintype "bidirectional"))
      (node (ref "IC5") (pin "10") (pinfunction "SCL_10") (pintype "bidirectional"))
      (node (ref "IC6") (pin "1") (pinfunction "ADDR_1") (pintype "bidirectional"))
      (node (ref "IC6") (pin "10") (pinfunction "SCL_10") (pintype "bidirectional"))
      (node (ref "J1") (pin "5") (pinfunction "5_5") (pintype "bidirectional"))
      (node (ref "R3") (pin "1") (pinfunction "1_1") (pintype "passive"))
      (node (ref "U$4") (pin "P$2") (pinfunction "2_P$2") (pintype "passive"))
    )
    (net (code "62") (name "SDA") (class "Default")
      (node (ref "AC1") (pin "13") (pinfunction "SDA/SDI/SDIO_13") (pintype "bidirectional"))
      (node (ref "IC4") (pin "9") (pinfunction "SDA_9") (pintype "bidirectional"))
      (node (ref "IC5") (pin "9") (pinfunction "SDA_9") (pintype "bidirectional"))
      (node (ref "IC6") (pin "9") (pinfunction "SDA_9") (pintype "bidirectional"))
      (node (ref "J1") (pin "3") (pinfunction "3_3") (pintype "bidirectional"))
      (node (ref "R2") (pin "1") (pinfunction "1_1") (pintype "passive"))
      (node (ref "U$4") (pin "P$3") (pinfunction "3_P$3") (pintype "passive"))
    )
    (net (code "63") (name "TMP1") (class "Default")
      (node (ref "IC5") (pin "7") (pinfunction "AIN3_7") (pintype "input"))
      (node (ref "J7") (pin "7") (pinfunction "7_7") (pintype "bidirectional"))
    )
    (net (code "64") (name "TMP2") (class "Default")
      (node (ref "IC5") (pin "6") (pinfunction "AIN2_6") (pintype "input"))
      (node (ref "J7") (pin "9") (pinfunction "9_9") (pintype "bidirectional"))
    )
    (net (code "65") (name "TMP3") (class "Default")
      (node (ref "IC5") (pin "5") (pinfunction "AIN1_5") (pintype "input"))
      (node (ref "IC7") (pin "2") (pinfunction "+VS_2") (pintype "bidirectional"))
    )
    (net (code "66") (name "unconnected-(AC1-INT1-Pad8)") (class "Default")
      (node (ref "AC1") (pin "8") (pinfunction "INT1_8") (pintype "bidirectional"))
    )
    (net (code "67") (name "unconnected-(AC1-INT2-Pad9)") (class "Default")
      (node (ref "AC1") (pin "9") (pinfunction "INT2_9") (pintype "bidirectional"))
    )
    (net (code "68") (name "unconnected-(AC1-NC-Pad10)") (class "Default")
      (node (ref "AC1") (pin "10") (pinfunction "NC_10") (pintype "no_connect"))
    )
    (net (code "69") (name "unconnected-(AC1-RESERVED_1-Pad3)") (class "Default")
      (node (ref "AC1") (pin "3") (pinfunction "RESERVED_1_3") (pintype "bidirectional"))
    )
    (net (code "70") (name "unconnected-(AC1-RESERVED_2-Pad11)") (class "Default")
      (node (ref "AC1") (pin "11") (pinfunction "RESERVED_2_11") (pintype "bidirectional"))
    )
    (net (code "71") (name "unconnected-(IC1-PA0_[AD0]-Pad78)") (class "Default")
      (node (ref "IC1") (pin "78") (pinfunction "PA0_[AD0]_78") (pintype "bidirectional"))
    )
    (net (code "72") (name "unconnected-(IC1-PC0_[A8]-Pad53)") (class "Default")
      (node (ref "IC1") (pin "53") (pinfunction "PC0_[A8]_53") (pintype "bidirectional"))
    )
    (net (code "73") (name "unconnected-(IC1-PC1_[A9]-Pad54)") (class "Default")
      (node (ref "IC1") (pin "54") (pinfunction "PC1_[A9]_54") (pintype "bidirectional"))
    )
    (net (code "74") (name "unconnected-(IC1-PC2_[A10]-Pad55)") (class "Default")
      (node (ref "IC1") (pin "55") (pinfunction "PC2_[A10]_55") (pintype "bidirectional"))
    )
    (net (code "75") (name "unconnected-(IC1-PC3_[A11]-Pad56)") (class "Default")
      (node (ref "IC1") (pin "56") (pinfunction "PC3_[A11]_56") (pintype "bidirectional"))
    )
    (net (code "76") (name "unconnected-(IC1-PC4_[A12]-Pad57)") (class "Default")
      (node (ref "IC1") (pin "57") (pinfunction "PC4_[A12]_57") (pintype "bidirectional"))
    )
    (net (code "77") (name "unconnected-(IC1-PC5_[A13]-Pad58)") (class "Default")
      (node (ref "IC1") (pin "58") (pinfunction "PC5_[A13]_58") (pintype "bidirectional"))
    )
    (net (code "78") (name "unconnected-(IC1-PC6_[A14]-Pad59)") (class "Default")
      (node (ref "IC1") (pin "59") (pinfunction "PC6_[A14]_59") (pintype "bidirectional"))
    )
    (net (code "79") (name "unconnected-(IC1-PC7_[A15]-Pad60)") (class "Default")
      (node (ref "IC1") (pin "60") (pinfunction "PC7_[A15]_60") (pintype "bidirectional"))
    )
    (net (code "80") (name "unconnected-(IC1-PF0_[ADC0]-Pad97)") (class "Default")
      (node (ref "IC1") (pin "97") (pinfunction "PF0_[ADC0]_97") (pintype "bidirectional"))
    )
    (net (code "81") (name "unconnected-(IC1-PF1_[ADC1]-Pad96)") (class "Default")
      (node (ref "IC1") (pin "96") (pinfunction "PF1_[ADC1]_96") (pintype "bidirectional"))
    )
    (net (code "82") (name "unconnected-(IC1-PF2_[ADC2]-Pad95)") (class "Default")
      (node (ref "IC1") (pin "95") (pinfunction "PF2_[ADC2]_95") (pintype "bidirectional"))
    )
    (net (code "83") (name "unconnected-(IC1-PF3_[ADC3]-Pad94)") (class "Default")
      (node (ref "IC1") (pin "94") (pinfunction "PF3_[ADC3]_94") (pintype "bidirectional"))
    )
    (net (code "84") (name "unconnected-(IC1-PF4_[ADC4{slash}TCK]-Pad93)") (class "Default")
      (node (ref "IC1") (pin "93") (pinfunction "PF4_[ADC4/TCK]_93") (pintype "bidirectional"))
    )
    (net (code "85") (name "unconnected-(IC1-PF5_[ADC5{slash}TMS]-Pad92)") (class "Default")
      (node (ref "IC1") (pin "92") (pinfunction "PF5_[ADC5/TMS]_92") (pintype "bidirectional"))
    )
    (net (code "86") (name "unconnected-(IC1-PF6_[ADC6{slash}TDO]-Pad91)") (class "Default")
      (node (ref "IC1") (pin "91") (pinfunction "PF6_[ADC6/TDO]_91") (pintype "bidirectional"))
    )
    (net (code "87") (name "unconnected-(IC1-PF7_[ADC7{slash}TDI]-Pad90)") (class "Default")
      (node (ref "IC1") (pin "90") (pinfunction "PF7_[ADC7/TDI]_90") (pintype "bidirectional"))
    )
    (net (code "88") (name "unconnected-(IC1-PG0_[~{WR]}-Pad51)") (class "Default")
      (node (ref "IC1") (pin "51") (pinfunction "PG0_[~{WR]}_51") (pintype "bidirectional"))
    )
    (net (code "89") (name "unconnected-(IC1-PG1_[~{RD]}-Pad52)") (class "Default")
      (node (ref "IC1") (pin "52") (pinfunction "PG1_[~{RD]}_52") (pintype "bidirectional"))
    )
    (net (code "90") (name "unconnected-(IC1-PJ0_[RXD3{slash}PCINT9]-Pad63)") (class "Default")
      (node (ref "IC1") (pin "63") (pinfunction "PJ0_[RXD3/PCINT9]_63") (pintype "input"))
    )
    (net (code "91") (name "unconnected-(IC1-PJ1_[TXD3{slash}PCINT10]-Pad64)") (class "Default")
      (node (ref "IC1") (pin "64") (pinfunction "PJ1_[TXD3/PCINT10]_64") (pintype "input"))
    )
    (net (code "92") (name "unconnected-(IC1-PJ2_[XCK3{slash}PCINT11]-Pad65)") (class "Default")
      (node (ref "IC1") (pin "65") (pinfunction "PJ2_[XCK3/PCINT11]_65") (pintype "input"))
    )
    (net (code "93") (name "unconnected-(IC1-PJ3_[PCINT12]-Pad66)") (class "Default")
      (node (ref "IC1") (pin "66") (pinfunction "PJ3_[PCINT12]_66") (pintype "input"))
    )
    (net (code "94") (name "unconnected-(IC1-PJ4_[PCINT13]-Pad67)") (class "Default")
      (node (ref "IC1") (pin "67") (pinfunction "PJ4_[PCINT13]_67") (pintype "input"))
    )
    (net (code "95") (name "unconnected-(IC1-PJ5_[PCINT14]-Pad68)") (class "Default")
      (node (ref "IC1") (pin "68") (pinfunction "PJ5_[PCINT14]_68") (pintype "input"))
    )
    (net (code "96") (name "unconnected-(IC1-PJ6_[PCINT15]-Pad69)") (class "Default")
      (node (ref "IC1") (pin "69") (pinfunction "PJ6_[PCINT15]_69") (pintype "input"))
    )
    (net (code "97") (name "unconnected-(IC1-PJ7-Pad79)") (class "Default")
      (node (ref "IC1") (pin "79") (pinfunction "PJ7_79") (pintype "bidirectional"))
    )
    (net (code "98") (name "unconnected-(IC1-PK0_[ADC8{slash}PCINT16]-Pad89)") (class "Default")
      (node (ref "IC1") (pin "89") (pinfunction "PK0_[ADC8/PCINT16]_89") (pintype "input"))
    )
    (net (code "99") (name "unconnected-(IC1-PK1_[ADC9{slash}PCINT17]-Pad88)") (class "Default")
      (node (ref "IC1") (pin "88") (pinfunction "PK1_[ADC9/PCINT17]_88") (pintype "input"))
    )
    (net (code "100") (name "unconnected-(IC1-PK2_[ADC10{slash}PCINT18]-Pad87)") (class "Default")
      (node (ref "IC1") (pin "87") (pinfunction "PK2_[ADC10/PCINT18]_87") (pintype "input"))
    )
    (net (code "101") (name "unconnected-(IC1-PK3_[ADC11{slash}PCINT19]-Pad86)") (class "Default")
      (node (ref "IC1") (pin "86") (pinfunction "PK3_[ADC11/PCINT19]_86") (pintype "input"))
    )
    (net (code "102") (name "unconnected-(IC1-PK4_[ADC12{slash}PCINT20]-Pad85)") (class "Default")
      (node (ref "IC1") (pin "85") (pinfunction "PK4_[ADC12/PCINT20]_85") (pintype "input"))
    )
    (net (code "103") (name "unconnected-(IC1-PK5_[ADC13{slash}PCINT21]-Pad84)") (class "Default")
      (node (ref "IC1") (pin "84") (pinfunction "PK5_[ADC13/PCINT21]_84") (pintype "input"))
    )
    (net (code "104") (name "unconnected-(IC1-PK6_[ADC14{slash}PCINT22]-Pad83)") (class "Default")
      (node (ref "IC1") (pin "83") (pinfunction "PK6_[ADC14/PCINT22]_83") (pintype "input"))
    )
    (net (code "105") (name "unconnected-(IC1-PK7_[ADC15{slash}PCINT23]-Pad82)") (class "Default")
      (node (ref "IC1") (pin "82") (pinfunction "PK7_[ADC15/PCINT23]_82") (pintype "input"))
    )
    (net (code "106") (name "unconnected-(IC1-PL7-Pad42)") (class "Default")
      (node (ref "IC1") (pin "42") (pinfunction "PL7_42") (pintype "bidirectional"))
    )
    (net (code "107") (name "unconnected-(IC1-[CLKO{slash}ICP3{slash}INT7]_PE7-Pad9)") (class "Default")
      (node (ref "IC1") (pin "9") (pinfunction "[CLKO/ICP3/INT7]_PE7_9") (pintype "output"))
    )
    (net (code "108") (name "unconnected-(IC1-[ICP1]_PD4-Pad47)") (class "Default")
      (node (ref "IC1") (pin "47") (pinfunction "[ICP1]_PD4_47") (pintype "bidirectional"))
    )
    (net (code "109") (name "unconnected-(IC1-[RXD1{slash}INT2]_PD2-Pad45)") (class "Default")
      (node (ref "IC1") (pin "45") (pinfunction "[RXD1/INT2]_PD2_45") (pintype "input"))
    )
    (net (code "110") (name "unconnected-(IC1-[RXD2]_PH0-Pad12)") (class "Default")
      (node (ref "IC1") (pin "12") (pinfunction "[RXD2]_PH0_12") (pintype "bidirectional"))
    )
    (net (code "111") (name "unconnected-(IC1-[SCL{slash}INT0]_PD0-Pad43)") (class "Default")
      (node (ref "IC1") (pin "43") (pinfunction "[SCL/INT0]_PD0_43") (pintype "input"))
    )
    (net (code "112") (name "unconnected-(IC1-[SDA{slash}INT1]_PD1-Pad44)") (class "Default")
      (node (ref "IC1") (pin "44") (pinfunction "[SDA/INT1]_PD1_44") (pintype "input"))
    )
    (net (code "113") (name "unconnected-(IC1-[T0]_PD7-Pad50)") (class "Default")
      (node (ref "IC1") (pin "50") (pinfunction "[T0]_PD7_50") (pintype "bidirectional"))
    )
    (net (code "114") (name "unconnected-(IC1-[T1]_PD6-Pad49)") (class "Default")
      (node (ref "IC1") (pin "49") (pinfunction "[T1]_PD6_49") (pintype "bidirectional"))
    )
    (net (code "115") (name "unconnected-(IC1-[T3{slash}INT6]_PE6-Pad8)") (class "Default")
      (node (ref "IC1") (pin "8") (pinfunction "[T3/INT6]_PE6_8") (pintype "input"))
    )
    (net (code "116") (name "unconnected-(IC1-[T4]_PH7-Pad27)") (class "Default")
      (node (ref "IC1") (pin "27") (pinfunction "[T4]_PH7_27") (pintype "bidirectional"))
    )
    (net (code "117") (name "unconnected-(IC1-[TOSC1]_PG4-Pad29)") (class "Default")
      (node (ref "IC1") (pin "29") (pinfunction "[TOSC1]_PG4_29") (pintype "bidirectional"))
    )
    (net (code "118") (name "unconnected-(IC1-[TOSC2]_PG3-Pad28)") (class "Default")
      (node (ref "IC1") (pin "28") (pinfunction "[TOSC2]_PG3_28") (pintype "bidirectional"))
    )
    (net (code "119") (name "unconnected-(IC1-[TXD1{slash}INT3]_PD3-Pad46)") (class "Default")
      (node (ref "IC1") (pin "46") (pinfunction "[TXD1/INT3]_PD3_46") (pintype "input"))
    )
    (net (code "120") (name "unconnected-(IC1-[TXD2]_PH1-Pad13)") (class "Default")
      (node (ref "IC1") (pin "13") (pinfunction "[TXD2]_PH1_13") (pintype "bidirectional"))
    )
    (net (code "121") (name "unconnected-(IC1-[XCK0{slash}AIN0]_PE2-Pad4)") (class "Default")
      (node (ref "IC1") (pin "4") (pinfunction "[XCK0/AIN0]_PE2_4") (pintype "input"))
    )
    (net (code "122") (name "unconnected-(IC1-[XCK1]_PD5-Pad48)") (class "Default")
      (node (ref "IC1") (pin "48") (pinfunction "[XCK1]_PD5_48") (pintype "bidirectional"))
    )
    (net (code "123") (name "unconnected-(IC1-[XCK2]_PH2-Pad14)") (class "Default")
      (node (ref "IC1") (pin "14") (pinfunction "[XCK2]_PH2_14") (pintype "bidirectional"))
    )
    (net (code "124") (name "unconnected-(IC1-[~{SS}{slash}PCINT0]_PB0-Pad19)") (class "Default")
      (node (ref "IC1") (pin "19") (pinfunction "[~{SS}/PCINT0]_PB0_19") (pintype "input"))
    )
    (net (code "125") (name "unconnected-(IC2-EP-Pad21)") (class "Default")
      (node (ref "IC2") (pin "21") (pinfunction "EP_21") (pintype "bidirectional"))
    )
    (net (code "126") (name "unconnected-(IC2-NC-Pad3)") (class "Default")
      (node (ref "IC2") (pin "3") (pinfunction "NC_3") (pintype "no_connect"))
    )
    (net (code "127") (name "unconnected-(IC2-NC_1-Pad18)") (class "Default")
      (node (ref "IC2") (pin "18") (pinfunction "NC_1_18") (pintype "bidirectional"))
    )
    (net (code "128") (name "unconnected-(IC2-SENSE_A-Pad2)") (class "Default")
      (node (ref "IC2") (pin "2") (pinfunction "SENSE_A_2") (pintype "input"))
    )
    (net (code "129") (name "unconnected-(IC2-SENSE_B-Pad19)") (class "Default")
      (node (ref "IC2") (pin "19") (pinfunction "SENSE_B_19") (pintype "input"))
    )
    (net (code "130") (name "unconnected-(IC3-EP-Pad21)") (class "Default")
      (node (ref "IC3") (pin "21") (pinfunction "EP_21") (pintype "bidirectional"))
    )
    (net (code "131") (name "unconnected-(IC3-NC-Pad3)") (class "Default")
      (node (ref "IC3") (pin "3") (pinfunction "NC_3") (pintype "no_connect"))
    )
    (net (code "132") (name "unconnected-(IC3-NC_1-Pad18)") (class "Default")
      (node (ref "IC3") (pin "18") (pinfunction "NC_1_18") (pintype "bidirectional"))
    )
    (net (code "133") (name "unconnected-(IC3-SENSE_A-Pad2)") (class "Default")
      (node (ref "IC3") (pin "2") (pinfunction "SENSE_A_2") (pintype "input"))
    )
    (net (code "134") (name "unconnected-(IC3-SENSE_B-Pad19)") (class "Default")
      (node (ref "IC3") (pin "19") (pinfunction "SENSE_B_19") (pintype "input"))
    )
    (net (code "135") (name "unconnected-(IC4-ALERT{slash}RDY-Pad2)") (class "Default")
      (node (ref "IC4") (pin "2") (pinfunction "ALERT/RDY_2") (pintype "bidirectional"))
    )
    (net (code "136") (name "unconnected-(IC5-AIN0-Pad4)") (class "Default")
      (node (ref "IC5") (pin "4") (pinfunction "AIN0_4") (pintype "input"))
    )
    (net (code "137") (name "unconnected-(IC5-ALERT{slash}RDY-Pad2)") (class "Default")
      (node (ref "IC5") (pin "2") (pinfunction "ALERT/RDY_2") (pintype "bidirectional"))
    )
    (net (code "138") (name "unconnected-(IC6-ALERT{slash}RDY-Pad2)") (class "Default")
      (node (ref "IC6") (pin "2") (pinfunction "ALERT/RDY_2") (pintype "bidirectional"))
    )
    (net (code "139") (name "unconnected-(IC7-NC-Pad3)") (class "Default")
      (node (ref "IC7") (pin "3") (pinfunction "NC_3") (pintype "no_connect"))
    )
    (net (code "140") (name "unconnected-(IC7-~{SHDN}-Pad4)") (class "Default")
      (node (ref "IC7") (pin "4") (pinfunction "~{SHDN}_4") (pintype "bidirectional"))
    )
    (net (code "141") (name "unconnected-(J1-Pad7)") (class "Default")
      (node (ref "J1") (pin "7") (pinfunction "7_7") (pintype "bidirectional"))
    )
    (net (code "142") (name "unconnected-(J1-Pad8)") (class "Default")
      (node (ref "J1") (pin "8") (pinfunction "8_8") (pintype "bidirectional"))
    )
    (net (code "143") (name "unconnected-(J1-Pad10)") (class "Default")
      (node (ref "J1") (pin "10") (pinfunction "10_10") (pintype "bidirectional"))
    )
    (net (code "144") (name "unconnected-(J1-Pad11)") (class "Default")
      (node (ref "J1") (pin "11") (pinfunction "11_11") (pintype "bidirectional"))
    )
    (net (code "145") (name "unconnected-(J1-Pad12)") (class "Default")
      (node (ref "J1") (pin "12") (pinfunction "12_12") (pintype "bidirectional"))
    )
    (net (code "146") (name "unconnected-(J1-Pad13)") (class "Default")
      (node (ref "J1") (pin "13") (pinfunction "13_13") (pintype "bidirectional"))
    )
    (net (code "147") (name "unconnected-(J1-Pad14)") (class "Default")
      (node (ref "J1") (pin "14") (pinfunction "14_14") (pintype "bidirectional"))
    )
    (net (code "148") (name "unconnected-(J1-Pad15)") (class "Default")
      (node (ref "J1") (pin "15") (pinfunction "15_15") (pintype "bidirectional"))
    )
    (net (code "149") (name "unconnected-(J1-Pad16)") (class "Default")
      (node (ref "J1") (pin "16") (pinfunction "16_16") (pintype "bidirectional"))
    )
    (net (code "150") (name "unconnected-(J1-Pad17)") (class "Default")
      (node (ref "J1") (pin "17") (pinfunction "17_17") (pintype "bidirectional"))
    )
    (net (code "151") (name "unconnected-(J1-Pad18)") (class "Default")
      (node (ref "J1") (pin "18") (pinfunction "18_18") (pintype "bidirectional"))
    )
    (net (code "152") (name "unconnected-(J1-Pad20)") (class "Default")
      (node (ref "J1") (pin "20") (pinfunction "20_20") (pintype "bidirectional"))
    )
    (net (code "153") (name "unconnected-(J1-Pad22)") (class "Default")
      (node (ref "J1") (pin "22") (pinfunction "22_22") (pintype "bidirectional"))
    )
    (net (code "154") (name "unconnected-(J1-Pad23)") (class "Default")
      (node (ref "J1") (pin "23") (pinfunction "23_23") (pintype "bidirectional"))
    )
    (net (code "155") (name "unconnected-(J1-Pad24)") (class "Default")
      (node (ref "J1") (pin "24") (pinfunction "24_24") (pintype "bidirectional"))
    )
    (net (code "156") (name "unconnected-(J1-Pad25)") (class "Default")
      (node (ref "J1") (pin "25") (pinfunction "25_25") (pintype "bidirectional"))
    )
    (net (code "157") (name "unconnected-(J1-Pad26)") (class "Default")
      (node (ref "J1") (pin "26") (pinfunction "26_26") (pintype "bidirectional"))
    )
    (net (code "158") (name "unconnected-(J1-Pad27)") (class "Default")
      (node (ref "J1") (pin "27") (pinfunction "27_27") (pintype "bidirectional"))
    )
    (net (code "159") (name "unconnected-(J1-Pad28)") (class "Default")
      (node (ref "J1") (pin "28") (pinfunction "28_28") (pintype "bidirectional"))
    )
    (net (code "160") (name "unconnected-(J1-Pad29)") (class "Default")
      (node (ref "J1") (pin "29") (pinfunction "29_29") (pintype "bidirectional"))
    )
    (net (code "161") (name "unconnected-(J1-Pad30)") (class "Default")
      (node (ref "J1") (pin "30") (pinfunction "30_30") (pintype "bidirectional"))
    )
    (net (code "162") (name "unconnected-(J1-Pad31)") (class "Default")
      (node (ref "J1") (pin "31") (pinfunction "31_31") (pintype "bidirectional"))
    )
    (net (code "163") (name "unconnected-(J1-Pad32)") (class "Default")
      (node (ref "J1") (pin "32") (pinfunction "32_32") (pintype "bidirectional"))
    )
    (net (code "164") (name "unconnected-(J1-Pad33)") (class "Default")
      (node (ref "J1") (pin "33") (pinfunction "33_33") (pintype "bidirectional"))
    )
    (net (code "165") (name "unconnected-(J1-Pad35)") (class "Default")
      (node (ref "J1") (pin "35") (pinfunction "35_35") (pintype "bidirectional"))
    )
    (net (code "166") (name "unconnected-(J1-Pad36)") (class "Default")
      (node (ref "J1") (pin "36") (pinfunction "36_36") (pintype "bidirectional"))
    )
    (net (code "167") (name "unconnected-(J1-Pad37)") (class "Default")
      (node (ref "J1") (pin "37") (pinfunction "37_37") (pintype "bidirectional"))
    )
    (net (code "168") (name "unconnected-(J1-Pad38)") (class "Default")
      (node (ref "J1") (pin "38") (pinfunction "38_38") (pintype "bidirectional"))
    )
    (net (code "169") (name "unconnected-(J1-Pad40)") (class "Default")
      (node (ref "J1") (pin "40") (pinfunction "40_40") (pintype "bidirectional"))
    )
    (net (code "170") (name "unconnected-(J7-Pad2)") (class "Default")
      (node (ref "J7") (pin "2") (pinfunction "2_2") (pintype "bidirectional"))
    )
    (net (code "171") (name "unconnected-(J7-Pad5)") (class "Default")
      (node (ref "J7") (pin "5") (pinfunction "5_5") (pintype "bidirectional"))
    )
    (net (code "172") (name "unconnected-(JP1-Pad2)") (class "Default")
      (node (ref "JP1") (pin "2") (pinfunction "2_2") (pintype "passive"))
    )
    (net (code "173") (name "unconnected-(JP2-Pad2)") (class "Default")
      (node (ref "JP2") (pin "2") (pinfunction "2_2") (pintype "passive"))
    )
  )
)
